# Real_Time_Clock.net
KiCad netlist of a schematic drawn in Altium Designer
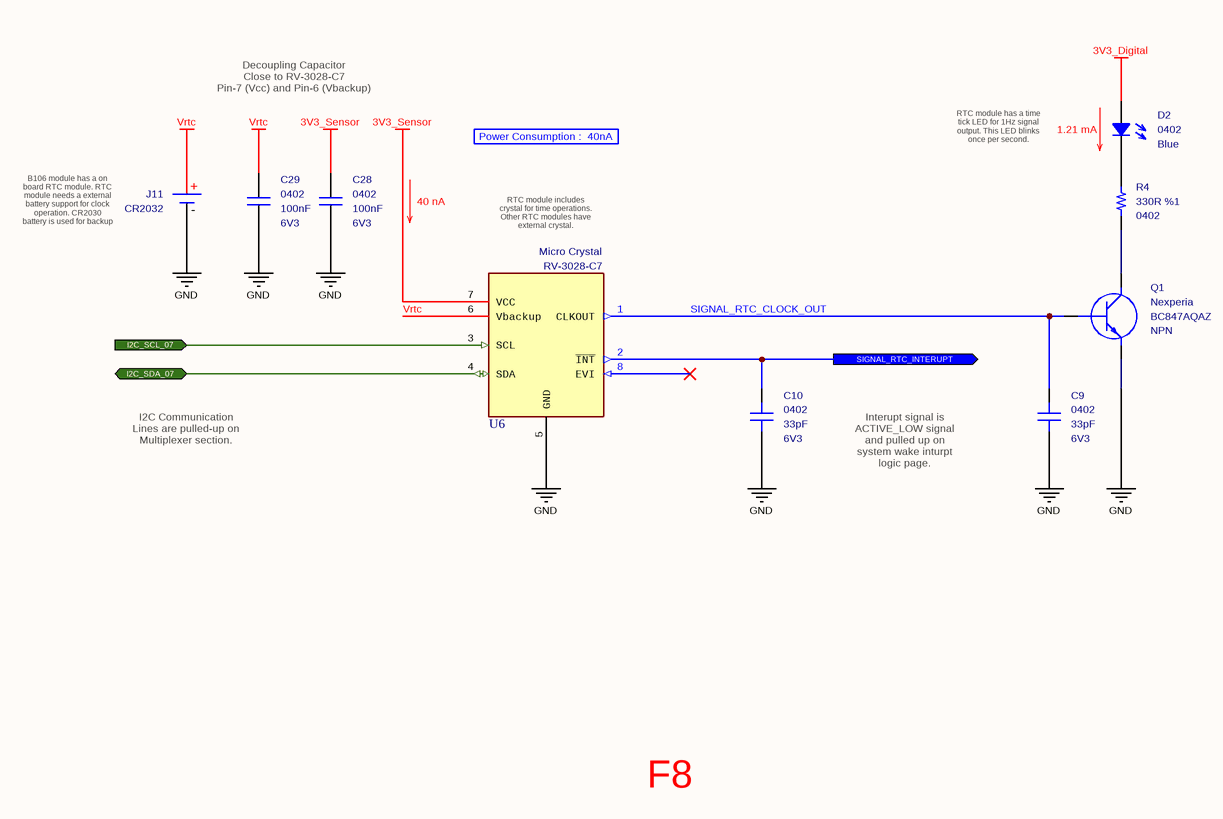
[diagram p0: Real Time Clock.SchDoc]

(export (version "E")
  (design (tool "Eeschema 10.0.6"))
  (components
    (comp (ref "C9")
      (value "33pF")
      (footprint "CAPACITOR_0402")
      (description "Capacitor - 33pF [0402] (Ceramic)")
      (fields
        (field (name "MANUFACTURER_PART_NUMBER") "C0402C330J9RACAUTO")
        (field (name "MOUSER_PART_NUMBER") "80-C0402C330J9RAUTO")
        (field (name "CASE") "0402")
        (field (name "VOLTAGE") "6V3")
      )
      (libsource (lib "Ovoo_Schematic") (part "Capacitor - 33pF [0402-6V3]"))
    )
    (comp (ref "C10")
      (value "33pF")
      (footprint "CAPACITOR_0402")
      (description "Capacitor - 33pF [0402] (Ceramic)")
      (fields
        (field (name "MANUFACTURER_PART_NUMBER") "C0402C330J9RACAUTO")
        (field (name "MOUSER_PART_NUMBER") "80-C0402C330J9RAUTO")
        (field (name "CASE") "0402")
        (field (name "VOLTAGE") "6V3")
      )
      (libsource (lib "Ovoo_Schematic") (part "Capacitor - 33pF [0402-6V3]"))
    )
    (comp (ref "C28")
      (value "100nF")
      (footprint "CAPACITOR_0402")
      (description "Capacitor - 100nF [0402-6V3] (Ceramic)")
      (fields
        (field (name "MANUFACTURER_PART_NUMBER") "04026D104KAT4A")
        (field (name "MOUSER_PART_NUMBER") "581-04026D104KAT4A")
        (field (name "CASE") "0402")
        (field (name "VOLTAGE") "6V3")
      )
      (libsource (lib "Ovoo_Schematic") (part "Capacitor - 100nF [0402-6V3]"))
    )
    (comp (ref "C29")
      (value "100nF")
      (footprint "CAPACITOR_0402")
      (description "Capacitor - 100nF [0402-6V3] (Ceramic)")
      (fields
        (field (name "MANUFACTURER_PART_NUMBER") "04026D104KAT4A")
        (field (name "MOUSER_PART_NUMBER") "581-04026D104KAT4A")
        (field (name "CASE") "0402")
        (field (name "VOLTAGE") "6V3")
      )
      (libsource (lib "Ovoo_Schematic") (part "Capacitor - 100nF [0402-6V3]"))
    )
    (comp (ref "D2")
      (value "SMD LED (Blue)")
      (footprint "LED_0402")
      (description "Standard LEDs - SMD PICOLEDTM;BLUE LED; 25M @ 5MA")
      (fields
        (field (name "MANUFACTURER_PART_NUMBER") "SMLP13BC8TT86")
        (field (name "MOUSER_PART_NUMBER") "755-SMLP13BC8TT86")
        (field (name "CASE") "0402")
        (field (name "COLOR") "Blue")
      )
      (libsource (lib "Ovoo_Schematic") (part "Diode - LED (0402-Blue)"))
    )
    (comp (ref "J11")
      (value "Battery Clip Holder and Battery")
      (footprint "BATTERY_HOLDER - CR2032")
      (description "Cylindrical Battery Contacts, Clips, Holders & Springs 16MM - 19MM SM BATTERY CLIP")
      (fields
        (field (name "MANUFACTURER_PART_NUMBER") "1070TR")
        (field (name "MOUSER_PART_NUMBER") "534-1070TR")
        (field (name "BATTERY SIZE") "CR2032")
      )
      (libsource (lib "Ovoo_Schematic") (part "Connector - Battery Holder (CR2032)"))
    )
    (comp (ref "Q1")
      (value "Bipolar NPN Transistors")
      (footprint "SOT1215")
      (description "Bipolar Transistors - BJT BC847AQA/DFN1010D-3/REEL 7\" Q2")
      (fields
        (field (name "MOUSER_PART_NUMBER") "771-BC847AQAZ")
        (field (name "MANUFACTURER_NAME") "Nexperia")
        (field (name "MANUFACTURER_PART_NUMBER") "BC847AQAZ")
        (field (name "POLARITY") "NPN")
      )
      (libsource (lib "Ovoo_Schematic") (part "Transistor - BC847"))
    )
    (comp (ref "R4")
      (value "330R")
      (footprint "RESISTOR_0402")
      (description "Thick Film Resistors - SMD 1/16 W 330 Ohm 1%")
      (fields
        (field (name "MANUFACTURER_PART_NUMBER") "CRCW0402330RFKED")
        (field (name "MOUSER_PART_NUMBER") "71-CRCW0402-330-E3")
        (field (name "TOLERANCE") "%1")
        (field (name "CASE") "0402")
      )
      (libsource (lib "Ovoo_Schematic") (part "Resistor - 330R"))
    )
    (comp (ref "U6")
      (value "Real Time Clock")
      (footprint "RV-3028-C7")
      (description "Real Time Clock 32.768kHz I2C Time Acc. 1ppm")
      (fields
        (field (name "MOUSER_PART_NUMBER") "428-203591-MG01")
        (field (name "MANUFACTURER_PART_NUMBER") "RV-3028-C7")
        (field (name "MANUFACTURER_NAME") "Micro Crystal")
      )
      (libsource (lib "Ovoo_Schematic") (part "IC - RV-3028-C7"))
    )
  )
  (nets
    (net (code "1") (name "/I2C_SCL_07") (class "Default")
      (node (ref "U6") (pin "3") (pinfunction "SCL_3") (pintype "input"))
    )
    (net (code "2") (name "/I2C_SDA_07") (class "Default")
      (node (ref "U6") (pin "4") (pinfunction "SDA_4") (pintype "bidirectional"))
    )
    (net (code "3") (name "/SIGNAL_RTC_CLOCK_OUT") (class "Default")
      (node (ref "C9") (pin "1") (pinfunction "1_1") (pintype "passive"))
      (node (ref "Q1") (pin "1") (pinfunction "B_1") (pintype "passive"))
      (node (ref "U6") (pin "1") (pinfunction "CLKOUT_1") (pintype "output"))
    )
    (net (code "4") (name "/SIGNAL_RTC_INTERUPT") (class "Default")
      (node (ref "C10") (pin "1") (pinfunction "1_1") (pintype "passive"))
      (node (ref "U6") (pin "2") (pinfunction "~{INT}_2") (pintype "output"))
    )
    (net (code "5") (name "3V3_Digital") (class "Default")
      (node (ref "D2") (pin "2") (pinfunction "2_2") (pintype "passive"))
    )
    (net (code "6") (name "3V3_Sensor") (class "Default")
      (node (ref "C28") (pin "2") (pinfunction "2_2") (pintype "passive"))
      (node (ref "U6") (pin "7") (pinfunction "VCC_7") (pintype "power_in"))
    )
    (net (code "7") (name "GND") (class "Default")
      (node (ref "C10") (pin "2") (pinfunction "2_2") (pintype "passive"))
      (node (ref "C28") (pin "1") (pinfunction "1_1") (pintype "passive"))
      (node (ref "C29") (pin "1") (pinfunction "1_1") (pintype "passive"))
      (node (ref "C9") (pin "2") (pinfunction "2_2") (pintype "passive"))
      (node (ref "J11") (pin "2") (pinfunction "BAT-_2") (pintype "power_in"))
      (node (ref "Q1") (pin "2") (pinfunction "E_2") (pintype "passive"))
      (node (ref "U6") (pin "5") (pinfunction "GND_5") (pintype "power_in"))
    )
    (net (code "8") (name "Net-(D2-Pad1)") (class "Default")
      (node (ref "D2") (pin "1") (pinfunction "1_1") (pintype "passive"))
      (node (ref "R4") (pin "2") (pinfunction "2_2") (pintype "passive"))
    )
    (net (code "9") (name "Net-(Q1-C)") (class "Default")
      (node (ref "Q1") (pin "3") (pinfunction "C_3") (pintype "passive"))
      (node (ref "R4") (pin "1") (pinfunction "1_1") (pintype "passive"))
    )
    (net (code "10") (name "Vrtc") (class "Default")
      (node (ref "C29") (pin "2") (pinfunction "2_2") (pintype "passive"))
      (node (ref "J11") (pin "1") (pinfunction "BAT+_1") (pintype "power_in"))
      (node (ref "U6") (pin "6") (pinfunction "Vbackup_6") (pintype "power_in"))
    )
    (net (code "11") (name "unconnected-(U6-EVI-Pad8)") (class "Default")
      (node (ref "U6") (pin "8") (pinfunction "EVI_8") (pintype "input+no_connect"))
    )
  )
)
